# LARSON-MH.net
KiCad netlist of a schematic drawn in EAGLE
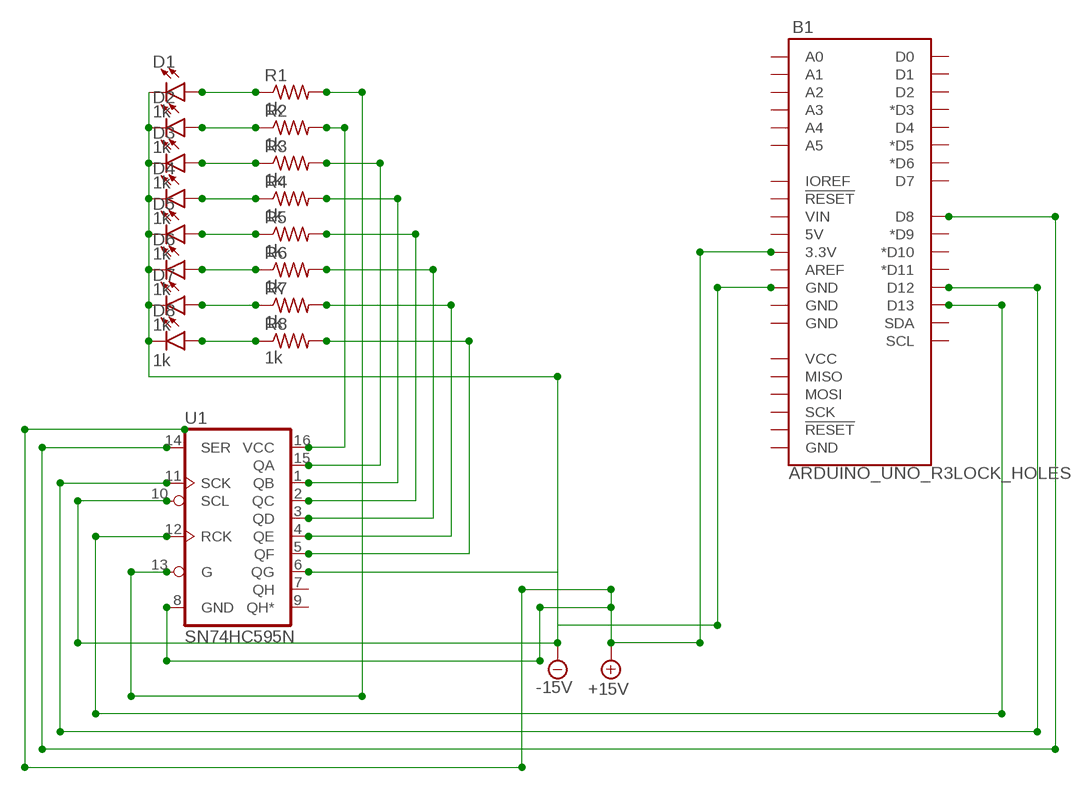
[diagram p0: schematic, sheet 1]

(export (version "E")
  (design (tool "Eeschema 10.0.6"))
  (components
    (comp (ref "B1")
      (value "ARDUINO_UNO_R3LOCK_HOLES")
      (footprint "eagle-import:ARDUINO_R3_LOCK_HOLES")
      (libsource (lib "eagle-import") (part "ARDUINO_UNO_R3LOCK_HOLES"))
    )
    (comp (ref "D1")
      (value "1k")
      (footprint "eagle-import:LED_5MM")
      (libsource (lib "eagle-import") (part "LED5MM"))
    )
    (comp (ref "D2")
      (value "1k")
      (footprint "eagle-import:LED_5MM")
      (libsource (lib "eagle-import") (part "LED5MM"))
    )
    (comp (ref "D3")
      (value "1k")
      (footprint "eagle-import:LED_5MM")
      (libsource (lib "eagle-import") (part "LED5MM"))
    )
    (comp (ref "D4")
      (value "1k")
      (footprint "eagle-import:LED_5MM")
      (libsource (lib "eagle-import") (part "LED5MM"))
    )
    (comp (ref "D5")
      (value "1k")
      (footprint "eagle-import:LED_5MM")
      (libsource (lib "eagle-import") (part "LED5MM"))
    )
    (comp (ref "D6")
      (value "1k")
      (footprint "eagle-import:LED_5MM")
      (libsource (lib "eagle-import") (part "LED5MM"))
    )
    (comp (ref "D7")
      (value "1k")
      (footprint "eagle-import:LED_5MM")
      (libsource (lib "eagle-import") (part "LED5MM"))
    )
    (comp (ref "D8")
      (value "1k")
      (footprint "eagle-import:LED_5MM")
      (libsource (lib "eagle-import") (part "LED5MM"))
    )
    (comp (ref "R1")
      (value "1k")
      (footprint "eagle-import:R0603")
      (libsource (lib "eagle-import") (part "R-US_R0603"))
    )
    (comp (ref "R2")
      (value "1k")
      (footprint "eagle-import:R0603")
      (libsource (lib "eagle-import") (part "R-US_R0603"))
    )
    (comp (ref "R3")
      (value "1k")
      (footprint "eagle-import:R0603")
      (libsource (lib "eagle-import") (part "R-US_R0603"))
    )
    (comp (ref "R4")
      (value "1k")
      (footprint "eagle-import:R0603")
      (libsource (lib "eagle-import") (part "R-US_R0603"))
    )
    (comp (ref "R5")
      (value "1k")
      (footprint "eagle-import:R0603")
      (libsource (lib "eagle-import") (part "R-US_R0603"))
    )
    (comp (ref "R6")
      (value "1k")
      (footprint "eagle-import:R0603")
      (libsource (lib "eagle-import") (part "R-US_R0603"))
    )
    (comp (ref "R7")
      (value "1k")
      (footprint "eagle-import:R0603")
      (libsource (lib "eagle-import") (part "R-US_R0603"))
    )
    (comp (ref "R8")
      (value "1k")
      (footprint "eagle-import:R0603")
      (libsource (lib "eagle-import") (part "R-US_R0603"))
    )
    (comp (ref "U1")
      (value "SN74HC595N")
      (footprint "eagle-import:DIP16")
      (libsource (lib "eagle-import") (part "74595NHC"))
    )
  )
  (nets
    (net (code "1") (name "+15V") (class "Default")
      (node (ref "B1") (pin "3.3V") (pinfunction "3.3V_3.3V") (pintype "bidirectional"))
      (node (ref "U1") (pin "8") (pinfunction "GND_8") (pintype "power_in"))
    )
    (net (code "2") (name "-15V") (class "Default")
      (node (ref "B1") (pin "GND@4") (pinfunction "GND_GND@4") (pintype "bidirectional"))
      (node (ref "D1") (pin "K") (pinfunction "C_K") (pintype "passive"))
      (node (ref "D2") (pin "K") (pinfunction "C_K") (pintype "passive"))
      (node (ref "D3") (pin "K") (pinfunction "C_K") (pintype "passive"))
      (node (ref "D4") (pin "K") (pinfunction "C_K") (pintype "passive"))
      (node (ref "D5") (pin "K") (pinfunction "C_K") (pintype "passive"))
      (node (ref "D6") (pin "K") (pinfunction "C_K") (pintype "passive"))
      (node (ref "D7") (pin "K") (pinfunction "C_K") (pintype "passive"))
      (node (ref "D8") (pin "K") (pinfunction "C_K") (pintype "passive"))
      (node (ref "U1") (pin "10") (pinfunction "SCL_10") (pintype "input"))
      (node (ref "U1") (pin "6") (pinfunction "QG_6") (pintype "tri_state"))
    )
    (net (code "3") (name "Net-(D1-PadA)") (class "Default")
      (node (ref "D1") (pin "A") (pinfunction "A_A") (pintype "passive"))
      (node (ref "R1") (pin "1") (pinfunction "1_1") (pintype "passive"))
    )
    (net (code "4") (name "Net-(D2-PadA)") (class "Default")
      (node (ref "D2") (pin "A") (pinfunction "A_A") (pintype "passive"))
      (node (ref "R2") (pin "1") (pinfunction "1_1") (pintype "passive"))
    )
    (net (code "5") (name "Net-(D3-PadA)") (class "Default")
      (node (ref "D3") (pin "A") (pinfunction "A_A") (pintype "passive"))
      (node (ref "R3") (pin "1") (pinfunction "1_1") (pintype "passive"))
    )
    (net (code "6") (name "Net-(D4-PadA)") (class "Default")
      (node (ref "D4") (pin "A") (pinfunction "A_A") (pintype "passive"))
      (node (ref "R4") (pin "1") (pinfunction "1_1") (pintype "passive"))
    )
    (net (code "7") (name "Net-(D5-PadA)") (class "Default")
      (node (ref "D5") (pin "A") (pinfunction "A_A") (pintype "passive"))
      (node (ref "R5") (pin "1") (pinfunction "1_1") (pintype "passive"))
    )
    (net (code "8") (name "Net-(D6-PadA)") (class "Default")
      (node (ref "D6") (pin "A") (pinfunction "A_A") (pintype "passive"))
      (node (ref "R6") (pin "1") (pinfunction "1_1") (pintype "passive"))
    )
    (net (code "9") (name "Net-(D7-PadA)") (class "Default")
      (node (ref "D7") (pin "A") (pinfunction "A_A") (pintype "passive"))
      (node (ref "R7") (pin "1") (pinfunction "1_1") (pintype "passive"))
    )
    (net (code "10") (name "Net-(D8-PadA)") (class "Default")
      (node (ref "D8") (pin "A") (pinfunction "A_A") (pintype "passive"))
      (node (ref "R8") (pin "1") (pinfunction "1_1") (pintype "passive"))
    )
    (net (code "11") (name "Net-(U1-G)") (class "Default")
      (node (ref "R1") (pin "2") (pinfunction "2_2") (pintype "passive"))
      (node (ref "U1") (pin "13") (pinfunction "G_13") (pintype "input"))
    )
    (net (code "12") (name "Net-(U1-QA)") (class "Default")
      (node (ref "R3") (pin "2") (pinfunction "2_2") (pintype "passive"))
      (node (ref "U1") (pin "15") (pinfunction "QA_15") (pintype "tri_state"))
    )
    (net (code "13") (name "Net-(U1-QB)") (class "Default")
      (node (ref "R4") (pin "2") (pinfunction "2_2") (pintype "passive"))
      (node (ref "U1") (pin "1") (pinfunction "QB_1") (pintype "tri_state"))
    )
    (net (code "14") (name "Net-(U1-QC)") (class "Default")
      (node (ref "R5") (pin "2") (pinfunction "2_2") (pintype "passive"))
      (node (ref "U1") (pin "2") (pinfunction "QC_2") (pintype "tri_state"))
    )
    (net (code "15") (name "Net-(U1-QD)") (class "Default")
      (node (ref "R6") (pin "2") (pinfunction "2_2") (pintype "passive"))
      (node (ref "U1") (pin "3") (pinfunction "QD_3") (pintype "tri_state"))
    )
    (net (code "16") (name "Net-(U1-QE)") (class "Default")
      (node (ref "R7") (pin "2") (pinfunction "2_2") (pintype "passive"))
      (node (ref "U1") (pin "4") (pinfunction "QE_4") (pintype "tri_state"))
    )
    (net (code "17") (name "Net-(U1-QF)") (class "Default")
      (node (ref "R8") (pin "2") (pinfunction "2_2") (pintype "passive"))
      (node (ref "U1") (pin "5") (pinfunction "QF_5") (pintype "tri_state"))
    )
    (net (code "18") (name "Net-(U1-RCK)") (class "Default")
      (node (ref "B1") (pin "D13") (pinfunction "D13_D13") (pintype "bidirectional"))
      (node (ref "U1") (pin "12") (pinfunction "RCK_12") (pintype "input"))
    )
    (net (code "19") (name "Net-(U1-SCK)") (class "Default")
      (node (ref "B1") (pin "D12") (pinfunction "D12_D12") (pintype "bidirectional"))
      (node (ref "U1") (pin "11") (pinfunction "SCK_11") (pintype "input"))
    )
    (net (code "20") (name "Net-(U1-SER)") (class "Default")
      (node (ref "B1") (pin "D8") (pinfunction "D8_D8") (pintype "bidirectional"))
      (node (ref "U1") (pin "14") (pinfunction "SER_14") (pintype "input"))
    )
    (net (code "21") (name "Net-(U1-VCC)") (class "Default")
      (node (ref "R2") (pin "2") (pinfunction "2_2") (pintype "passive"))
      (node (ref "U1") (pin "16") (pinfunction "VCC_16") (pintype "power_in"))
    )
    (net (code "22") (name "unconnected-(B1-*D3-PadD3)") (class "Default")
      (node (ref "B1") (pin "D3") (pinfunction "*D3_D3") (pintype "bidirectional"))
    )
    (net (code "23") (name "unconnected-(B1-*D5-PadD5)") (class "Default")
      (node (ref "B1") (pin "D5") (pinfunction "*D5_D5") (pintype "bidirectional"))
    )
    (net (code "24") (name "unconnected-(B1-*D6-PadD6)") (class "Default")
      (node (ref "B1") (pin "D6") (pinfunction "*D6_D6") (pintype "bidirectional"))
    )
    (net (code "25") (name "unconnected-(B1-*D9-PadD9)") (class "Default")
      (node (ref "B1") (pin "D9") (pinfunction "*D9_D9") (pintype "bidirectional"))
    )
    (net (code "26") (name "unconnected-(B1-*D10-PadD10)") (class "Default")
      (node (ref "B1") (pin "D10") (pinfunction "*D10_D10") (pintype "bidirectional"))
    )
    (net (code "27") (name "unconnected-(B1-*D11-PadD11)") (class "Default")
      (node (ref "B1") (pin "D11") (pinfunction "*D11_D11") (pintype "bidirectional"))
    )
    (net (code "28") (name "unconnected-(B1-GND-PadGND@1)") (class "Default")
      (node (ref "B1") (pin "GND@1") (pinfunction "GND_GND@1") (pintype "bidirectional"))
    )
    (net (code "29") (name "unconnected-(B1-GND-PadGND@2)") (class "Default")
      (node (ref "B1") (pin "GND@2") (pinfunction "GND_GND@2") (pintype "bidirectional"))
    )
    (net (code "30") (name "unconnected-(B1-GND-PadGND@3)") (class "Default")
      (node (ref "B1") (pin "GND@3") (pinfunction "GND_GND@3") (pintype "bidirectional"))
    )
    (net (code "31") (name "unconnected-(B1-Pad5V)") (class "Default")
      (node (ref "B1") (pin "5V") (pinfunction "5V_5V") (pintype "bidirectional"))
    )
    (net (code "32") (name "unconnected-(B1-PadA0)") (class "Default")
      (node (ref "B1") (pin "A0") (pinfunction "A0_A0") (pintype "bidirectional"))
    )
    (net (code "33") (name "unconnected-(B1-PadA1)") (class "Default")
      (node (ref "B1") (pin "A1") (pinfunction "A1_A1") (pintype "bidirectional"))
    )
    (net (code "34") (name "unconnected-(B1-PadA2)") (class "Default")
      (node (ref "B1") (pin "A2") (pinfunction "A2_A2") (pintype "bidirectional"))
    )
    (net (code "35") (name "unconnected-(B1-PadA3)") (class "Default")
      (node (ref "B1") (pin "A3") (pinfunction "A3_A3") (pintype "bidirectional"))
    )
    (net (code "36") (name "unconnected-(B1-PadA4)") (class "Default")
      (node (ref "B1") (pin "A4") (pinfunction "A4_A4") (pintype "bidirectional"))
    )
    (net (code "37") (name "unconnected-(B1-PadA5)") (class "Default")
      (node (ref "B1") (pin "A5") (pinfunction "A5_A5") (pintype "bidirectional"))
    )
    (net (code "38") (name "unconnected-(B1-PadAREF)") (class "Default")
      (node (ref "B1") (pin "AREF") (pinfunction "AREF_AREF") (pintype "bidirectional"))
    )
    (net (code "39") (name "unconnected-(B1-PadD0)") (class "Default")
      (node (ref "B1") (pin "D0") (pinfunction "D0_D0") (pintype "bidirectional"))
    )
    (net (code "40") (name "unconnected-(B1-PadD1)") (class "Default")
      (node (ref "B1") (pin "D1") (pinfunction "D1_D1") (pintype "bidirectional"))
    )
    (net (code "41") (name "unconnected-(B1-PadD2)") (class "Default")
      (node (ref "B1") (pin "D2") (pinfunction "D2_D2") (pintype "bidirectional"))
    )
    (net (code "42") (name "unconnected-(B1-PadD4)") (class "Default")
      (node (ref "B1") (pin "D4") (pinfunction "D4_D4") (pintype "bidirectional"))
    )
    (net (code "43") (name "unconnected-(B1-PadD7)") (class "Default")
      (node (ref "B1") (pin "D7") (pinfunction "D7_D7") (pintype "bidirectional"))
    )
    (net (code "44") (name "unconnected-(B1-PadIOREF)") (class "Default")
      (node (ref "B1") (pin "IOREF") (pinfunction "IOREF_IOREF") (pintype "bidirectional"))
    )
    (net (code "45") (name "unconnected-(B1-PadMISO)") (class "Default")
      (node (ref "B1") (pin "MISO") (pinfunction "MISO_MISO") (pintype "bidirectional"))
    )
    (net (code "46") (name "unconnected-(B1-PadMOSI)") (class "Default")
      (node (ref "B1") (pin "MOSI") (pinfunction "MOSI_MOSI") (pintype "bidirectional"))
    )
    (net (code "47") (name "unconnected-(B1-PadSCK)") (class "Default")
      (node (ref "B1") (pin "SCK") (pinfunction "SCK_SCK") (pintype "bidirectional"))
    )
    (net (code "48") (name "unconnected-(B1-PadSCL)") (class "Default")
      (node (ref "B1") (pin "SCL") (pinfunction "SCL_SCL") (pintype "bidirectional"))
    )
    (net (code "49") (name "unconnected-(B1-PadSDA)") (class "Default")
      (node (ref "B1") (pin "SDA") (pinfunction "SDA_SDA") (pintype "bidirectional"))
    )
    (net (code "50") (name "unconnected-(B1-PadVCC)") (class "Default")
      (node (ref "B1") (pin "VCC") (pinfunction "VCC_VCC") (pintype "bidirectional"))
    )
    (net (code "51") (name "unconnected-(B1-PadVIN)") (class "Default")
      (node (ref "B1") (pin "VIN") (pinfunction "VIN_VIN") (pintype "bidirectional"))
    )
    (net (code "52") (name "unconnected-(B1-~{RESET}-PadRESET@1)") (class "Default")
      (node (ref "B1") (pin "RESET@1") (pinfunction "~{RESET}_RESET@1") (pintype "bidirectional"))
    )
    (net (code "53") (name "unconnected-(B1-~{RESET}-PadRESET@2)") (class "Default")
      (node (ref "B1") (pin "RESET@2") (pinfunction "~{RESET}_RESET@2") (pintype "bidirectional"))
    )
    (net (code "54") (name "unconnected-(U1-QH*-Pad9)") (class "Default")
      (node (ref "U1") (pin "9") (pinfunction "QH*_9") (pintype "tri_state"))
    )
    (net (code "55") (name "unconnected-(U1-QH-Pad7)") (class "Default")
      (node (ref "U1") (pin "7") (pinfunction "QH_7") (pintype "tri_state"))
    )
  )
)
